# mainboard_ESP32_DevBoard.net
KiCad netlist of a schematic drawn in EAGLE
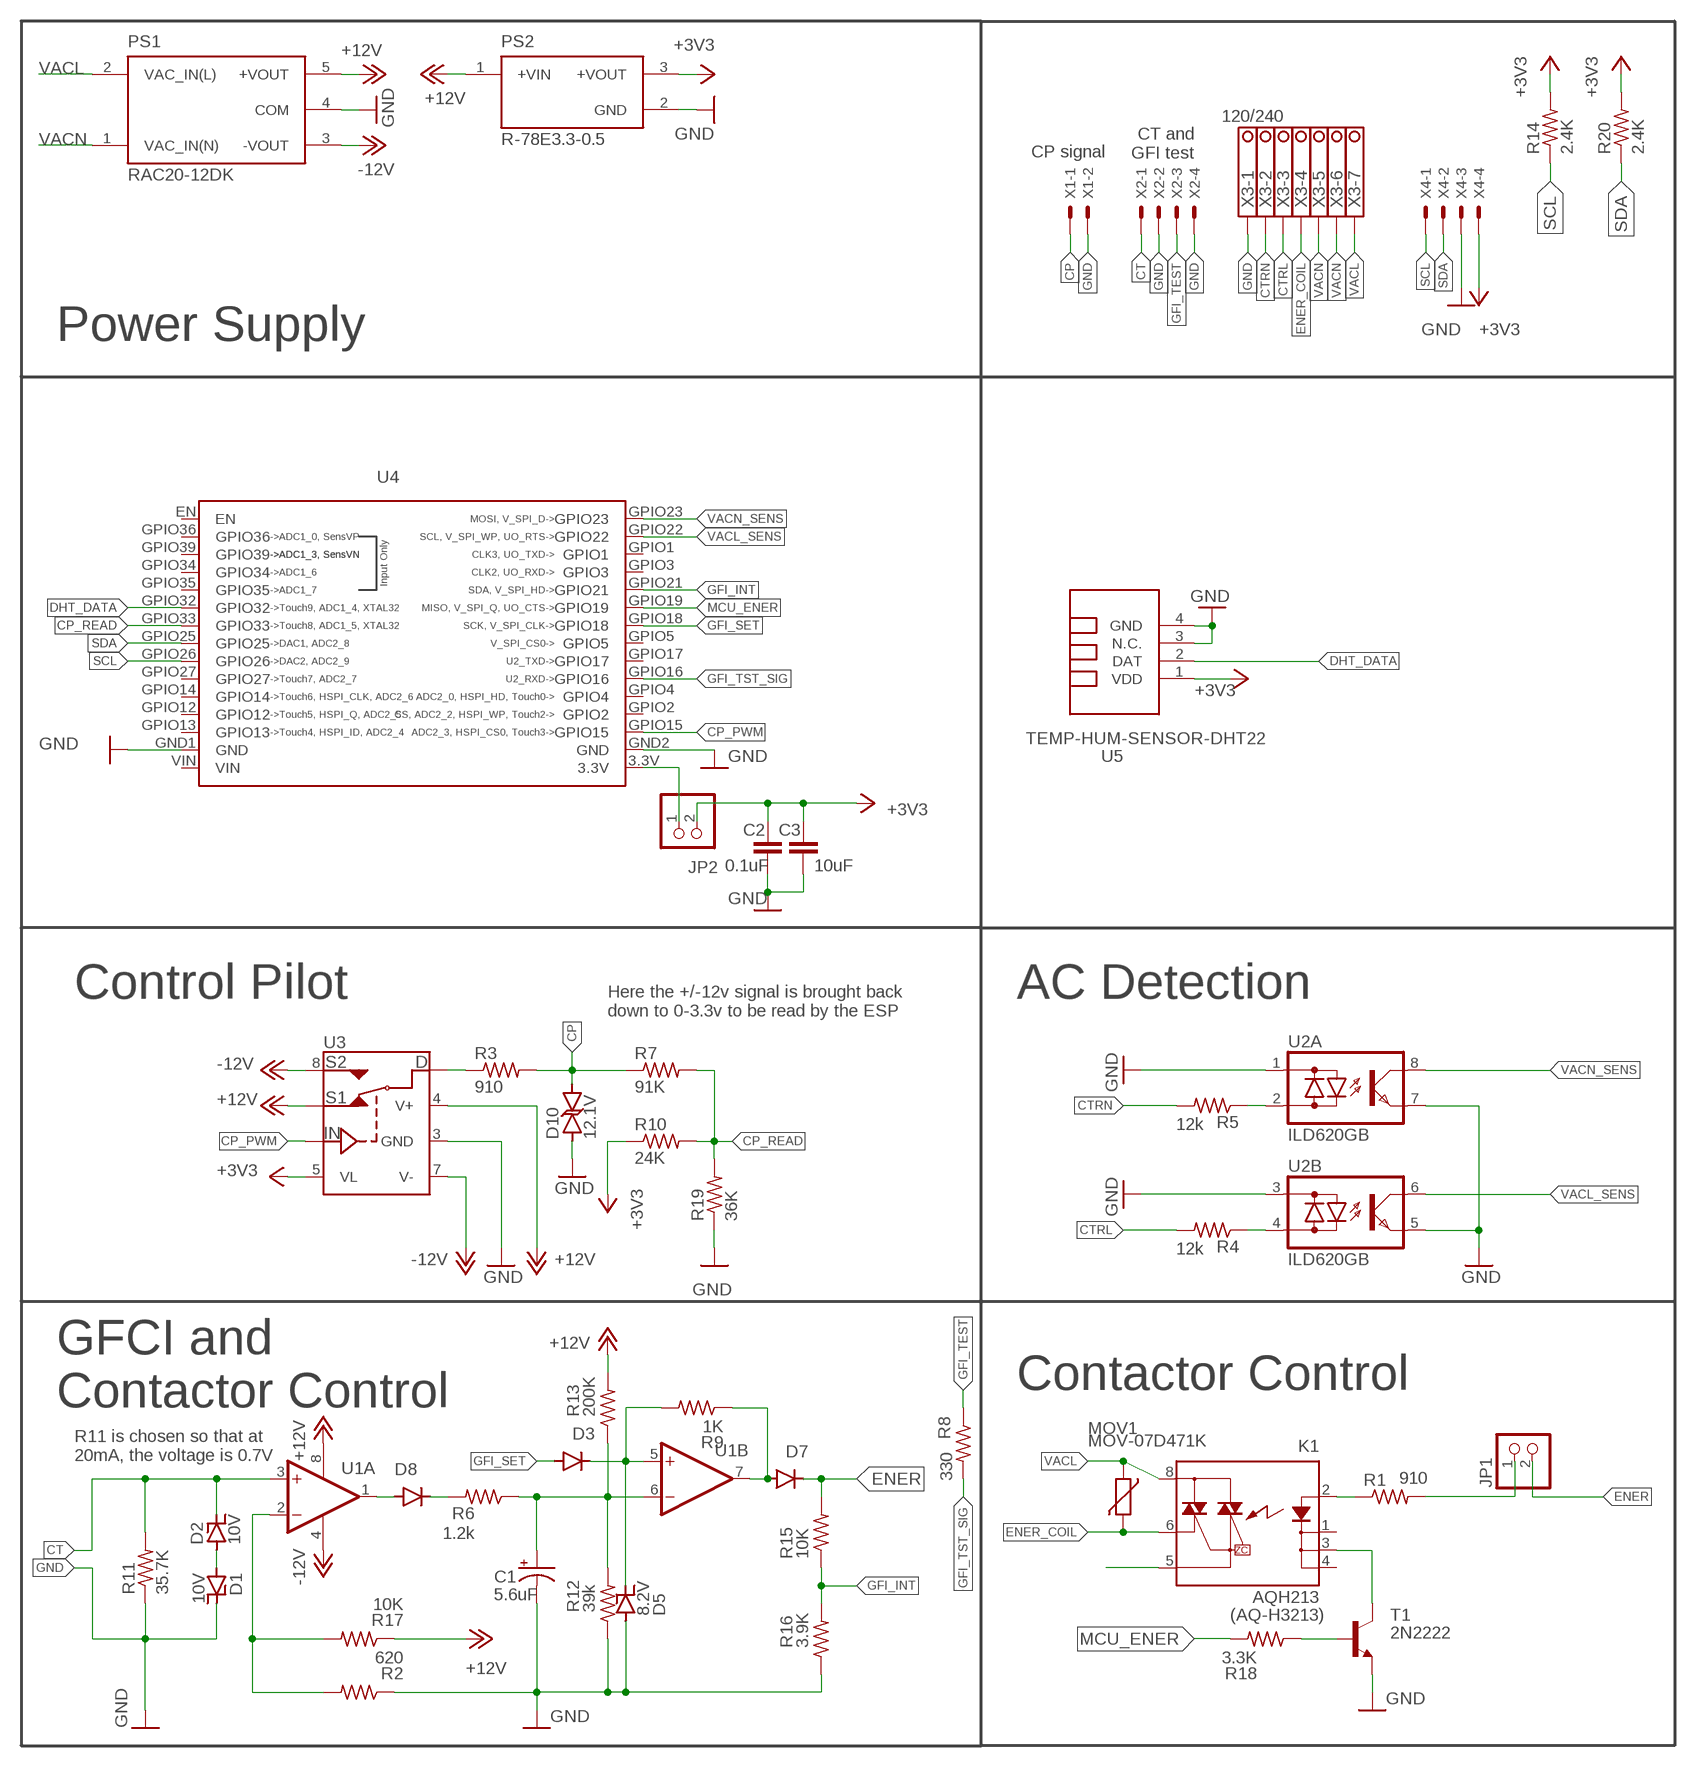
[diagram p0: schematic, sheet 1]

(export (version "E")
  (design (tool "Eeschema 10.0.6"))
  (components
    (comp (ref "C1")
      (value "5.6uF")
      (footprint "eagle-import:E2-5")
      (libsource (lib "eagle-import") (part "CPOL-USE2-5"))
    )
    (comp (ref "C2")
      (value "0.1uF")
      (footprint "eagle-import:C025-025X050")
      (libsource (lib "eagle-import") (part "C-EU025-025X050"))
    )
    (comp (ref "C3")
      (value "10uF")
      (footprint "eagle-import:C025-050X050")
      (libsource (lib "eagle-import") (part "C-EU025-050X050"))
    )
    (comp (ref "D1")
      (value "10V")
      (footprint "eagle-import:DO35-7")
      (libsource (lib "eagle-import") (part "ZENER"))
    )
    (comp (ref "D2")
      (value "10V")
      (footprint "eagle-import:DO35-7")
      (libsource (lib "eagle-import") (part "ZENER"))
    )
    (comp (ref "D3")
      (value "1N4148DO35-7")
      (footprint "eagle-import:DO35-7")
      (libsource (lib "eagle-import") (part "1N4148DO35-7"))
    )
    (comp (ref "D5")
      (value "8.2V")
      (footprint "eagle-import:DO35-7")
      (libsource (lib "eagle-import") (part "ZENER"))
    )
    (comp (ref "D7")
      (value "1N4148DO35-7")
      (footprint "eagle-import:DO35-7")
      (libsource (lib "eagle-import") (part "1N4148DO35-7"))
    )
    (comp (ref "D8")
      (value "1N4148DO35-7")
      (footprint "eagle-import:DO35-7")
      (libsource (lib "eagle-import") (part "1N4148DO35-7"))
    )
    (comp (ref "D10")
      (value "12.1V")
      (footprint "eagle-import:DO15")
      (libsource (lib "eagle-import") (part "P6KE15CAL"))
    )
    (comp (ref "JP1")
      (value "PINHD-1X2")
      (footprint "eagle-import:1X02")
      (libsource (lib "eagle-import") (part "PINHD-1X2"))
    )
    (comp (ref "JP2")
      (value "PINHD-1X2/90")
      (footprint "eagle-import:1X02_90")
      (libsource (lib "eagle-import") (part "PINHD-1X2/90"))
    )
    (comp (ref "K1")
      (value "AQH213")
      (footprint "eagle-import:DIL07")
      (libsource (lib "eagle-import") (part "AQH213"))
    )
    (comp (ref "MOV1")
      (value "MOV-07D471K")
      (footprint "eagle-import:DISC-7")
      (libsource (lib "eagle-import") (part "MOV-07D471K"))
    )
    (comp (ref "PS1")
      (value "RAC20-12DK")
      (footprint "eagle-import:CONV_RAC20-12DK")
      (fields (field (name "DIGI-KEY_PART_NUMBER") "945-3239-ND") (field (name "MF") "Recom Power"))
      (libsource (lib "eagle-import") (part "RAC20-12DK"))
    )
    (comp (ref "PS2")
      (value "R-78E3.3-0.5")
      (footprint "eagle-import:CONV_R-78E3.3-0.5")
      (fields (field (name "DIGI-KEY_PART_NUMBER") "945-1661-5-ND") (field (name "MF") "Recom Power"))
      (libsource (lib "eagle-import") (part "R-78E3.3-0.5"))
    )
    (comp (ref "R1")
      (value "910")
      (footprint "eagle-import:0204_7-L")
      (libsource (lib "eagle-import") (part "RESISTORL"))
    )
    (comp (ref "R2")
      (value "620")
      (footprint "eagle-import:0204_7-L")
      (libsource (lib "eagle-import") (part "RESISTORL"))
    )
    (comp (ref "R3")
      (value "910")
      (footprint "eagle-import:0204_7-L")
      (libsource (lib "eagle-import") (part "RESISTORL"))
    )
    (comp (ref "R4")
      (value "12k")
      (footprint "eagle-import:0204_7-L")
      (libsource (lib "eagle-import") (part "RESISTORL"))
    )
    (comp (ref "R5")
      (value "12k")
      (footprint "eagle-import:0204_7-L")
      (libsource (lib "eagle-import") (part "RESISTORL"))
    )
    (comp (ref "R6")
      (value "1.2k")
      (footprint "eagle-import:0204_7-L")
      (libsource (lib "eagle-import") (part "RESISTORL"))
    )
    (comp (ref "R7")
      (value "91K")
      (footprint "eagle-import:0204_7-L")
      (libsource (lib "eagle-import") (part "RESISTORL"))
    )
    (comp (ref "R8")
      (value "330")
      (footprint "eagle-import:0204_7-L")
      (libsource (lib "eagle-import") (part "RESISTORL"))
    )
    (comp (ref "R9")
      (value "1K")
      (footprint "eagle-import:0204_7-L")
      (libsource (lib "eagle-import") (part "RESISTORL"))
    )
    (comp (ref "R10")
      (value "24K")
      (footprint "eagle-import:0204_7-L")
      (libsource (lib "eagle-import") (part "RESISTORL"))
    )
    (comp (ref "R11")
      (value "35.7K")
      (footprint "eagle-import:0204_7-L")
      (libsource (lib "eagle-import") (part "RESISTORL"))
    )
    (comp (ref "R12")
      (value "39k")
      (footprint "eagle-import:0204_7-L")
      (libsource (lib "eagle-import") (part "RESISTORL"))
    )
    (comp (ref "R13")
      (value "200K")
      (footprint "eagle-import:0204_7-L")
      (libsource (lib "eagle-import") (part "RESISTORL"))
    )
    (comp (ref "R14")
      (value "2.4K")
      (footprint "eagle-import:0204_7-L")
      (libsource (lib "eagle-import") (part "RESISTORL"))
    )
    (comp (ref "R15")
      (value "10K")
      (footprint "eagle-import:0204_7-L")
      (libsource (lib "eagle-import") (part "RESISTORL"))
    )
    (comp (ref "R16")
      (value "3.9K")
      (footprint "eagle-import:0204_7-L")
      (libsource (lib "eagle-import") (part "RESISTORL"))
    )
    (comp (ref "R17")
      (value "10K")
      (footprint "eagle-import:0204_7-L")
      (libsource (lib "eagle-import") (part "RESISTORL"))
    )
    (comp (ref "R18")
      (value "3.3K")
      (footprint "eagle-import:0204_7-L")
      (libsource (lib "eagle-import") (part "RESISTORL"))
    )
    (comp (ref "R19")
      (value "36K")
      (footprint "eagle-import:0204_7-L")
      (libsource (lib "eagle-import") (part "RESISTORL"))
    )
    (comp (ref "R20")
      (value "2.4K")
      (footprint "eagle-import:0204_7-L")
      (libsource (lib "eagle-import") (part "RESISTORL"))
    )
    (comp (ref "T1")
      (value "2N2222")
      (footprint "eagle-import:TO92-EBC")
      (libsource (lib "eagle-import") (part "-NPN-TO92-EBC2N2222"))
    )
    (comp (ref "U1")
      (value "LM833N")
      (footprint "eagle-import:DIL08-LONG")
      (libsource (lib "eagle-import") (part "LM833N"))
    )
    (comp (ref "U2")
      (value "ILD620GB")
      (footprint "eagle-import:DIL8")
      (libsource (lib "eagle-import") (part "ILD620GB"))
    )
    (comp (ref "U3")
      (value "DG419DJ-L")
      (footprint "eagle-import:DIL08-LONG")
      (libsource (lib "eagle-import") (part "DG419DJ-L"))
    )
    (comp (ref "U4")
      (value "ESP32-DOIT-V1")
      (footprint "eagle-import:ESP32-DOIT-V1")
      (libsource (lib "eagle-import") (part "ESP32-DOIT-V1"))
    )
    (comp (ref "U5")
      (value "TEMP-HUM-SENSOR-DHT22")
      (footprint "eagle-import:TEMP-HUM-SENSOR-DHT22")
      (libsource (lib "eagle-import") (part "TEMP-HUM-SENSOR-DHT22"))
    )
    (comp (ref "X1")
      (value "JST-XH-02-PIN-LONG-PAD")
      (footprint "eagle-import:JST-XH-02-PACKAGE-LONG-PAD")
      (libsource (lib "eagle-import") (part "JST-XH-02-PIN-LONG-PAD"))
    )
    (comp (ref "X2")
      (value "JST-XH-04-PIN-LONG-PAD")
      (footprint "eagle-import:JST-XH-04-PACKAGE-LONG-PAD")
      (libsource (lib "eagle-import") (part "JST-XH-04-PIN-LONG-PAD"))
    )
    (comp (ref "X3")
      (value "1751293")
      (footprint "eagle-import:1751293")
      (libsource (lib "eagle-import") (part "1751293"))
    )
    (comp (ref "X4")
      (value "JST-XH-04-PIN-LONG-PAD")
      (footprint "eagle-import:JST-XH-04-PACKAGE-LONG-PAD")
      (libsource (lib "eagle-import") (part "JST-XH-04-PIN-LONG-PAD"))
    )
  )
  (nets
    (net (code "1") (name "+3V3") (class "Default")
      (node (ref "C2") (pin "1") (pinfunction "1_1") (pintype "passive"))
      (node (ref "C3") (pin "1") (pinfunction "1_1") (pintype "passive"))
      (node (ref "JP2") (pin "2") (pinfunction "2_2") (pintype "passive"))
      (node (ref "PS2") (pin "3") (pinfunction "+VOUT_3") (pintype "output"))
      (node (ref "R10") (pin "1") (pinfunction "1_1") (pintype "passive"))
      (node (ref "R14") (pin "2") (pinfunction "2_2") (pintype "passive"))
      (node (ref "R20") (pin "2") (pinfunction "2_2") (pintype "passive"))
      (node (ref "U3") (pin "5") (pinfunction "VL_5") (pintype "bidirectional"))
      (node (ref "U5") (pin "1") (pinfunction "VDD_1") (pintype "power_in"))
      (node (ref "X4") (pin "4") (pinfunction "S_4") (pintype "passive"))
    )
    (net (code "2") (name "+12V") (class "Default")
      (node (ref "PS1") (pin "5") (pinfunction "+VOUT_5") (pintype "output"))
      (node (ref "PS2") (pin "1") (pinfunction "+VIN_1") (pintype "input"))
      (node (ref "R13") (pin "2") (pinfunction "2_2") (pintype "passive"))
      (node (ref "R17") (pin "1") (pinfunction "1_1") (pintype "passive"))
      (node (ref "U1") (pin "8") (pinfunction "V+_8") (pintype "power_in"))
      (node (ref "U3") (pin "2") (pinfunction "S1_2") (pintype "input"))
      (node (ref "U3") (pin "4") (pinfunction "V+_4") (pintype "bidirectional"))
    )
    (net (code "3") (name "-12V") (class "Default")
      (node (ref "PS1") (pin "3") (pinfunction "-VOUT_3") (pintype "output"))
      (node (ref "U1") (pin "4") (pinfunction "V-_4") (pintype "power_in"))
      (node (ref "U3") (pin "7") (pinfunction "V-_7") (pintype "bidirectional"))
      (node (ref "U3") (pin "8") (pinfunction "S2_8") (pintype "input"))
    )
    (net (code "4") (name "/VIN") (class "Default")
      (node (ref "U4") (pin "VIN") (pinfunction "VIN_VIN") (pintype "power_in"))
    )
    (net (code "5") (name "CP") (class "Default")
      (node (ref "D10") (pin "C") (pinfunction "C_C") (pintype "passive"))
      (node (ref "R3") (pin "2") (pinfunction "2_2") (pintype "passive"))
      (node (ref "R7") (pin "1") (pinfunction "1_1") (pintype "passive"))
      (node (ref "X1") (pin "1") (pinfunction "S_1") (pintype "passive"))
    )
    (net (code "6") (name "CP_PWM") (class "Default")
      (node (ref "U3") (pin "6") (pinfunction "IN_6") (pintype "bidirectional"))
      (node (ref "U4") (pin "GPIO15") (pinfunction "GPIO15_GPIO15") (pintype "bidirectional"))
    )
    (net (code "7") (name "CP_READ") (class "Default")
      (node (ref "R10") (pin "2") (pinfunction "2_2") (pintype "passive"))
      (node (ref "R19") (pin "2") (pinfunction "2_2") (pintype "passive"))
      (node (ref "R7") (pin "2") (pinfunction "2_2") (pintype "passive"))
      (node (ref "U4") (pin "GPIO33") (pinfunction "GPIO33_GPIO33") (pintype "bidirectional"))
    )
    (net (code "8") (name "CT") (class "Default")
      (node (ref "D2") (pin "C") (pinfunction "C_C") (pintype "passive"))
      (node (ref "R11") (pin "2") (pinfunction "2_2") (pintype "passive"))
      (node (ref "U1") (pin "3") (pinfunction "+IN_3") (pintype "input"))
      (node (ref "X2") (pin "1") (pinfunction "S_1") (pintype "passive"))
    )
    (net (code "9") (name "CTRL") (class "Default")
      (node (ref "R4") (pin "2") (pinfunction "2_2") (pintype "passive"))
      (node (ref "X3") (pin "3") (pinfunction "K_3") (pintype "passive"))
    )
    (net (code "10") (name "CTRN") (class "Default")
      (node (ref "R5") (pin "2") (pinfunction "2_2") (pintype "passive"))
      (node (ref "X3") (pin "2") (pinfunction "K_2") (pintype "passive"))
    )
    (net (code "11") (name "DHT_DATA") (class "Default")
      (node (ref "U4") (pin "GPIO32") (pinfunction "GPIO32_GPIO32") (pintype "bidirectional"))
      (node (ref "U5") (pin "2") (pinfunction "DAT_2") (pintype "bidirectional"))
    )
    (net (code "12") (name "ENER") (class "Default")
      (node (ref "D7") (pin "C") (pinfunction "C_C") (pintype "passive"))
      (node (ref "JP1") (pin "2") (pinfunction "2_2") (pintype "passive"))
      (node (ref "R15") (pin "2") (pinfunction "2_2") (pintype "passive"))
    )
    (net (code "13") (name "ENER_COIL") (class "Default")
      (node (ref "K1") (pin "6") (pinfunction "DS3_6") (pintype "passive"))
      (node (ref "MOV1") (pin "P$2") (pinfunction "2_P$2") (pintype "passive"))
      (node (ref "X3") (pin "4") (pinfunction "K_4") (pintype "passive"))
    )
    (net (code "14") (name "GFI_INT") (class "Default")
      (node (ref "R15") (pin "1") (pinfunction "1_1") (pintype "passive"))
      (node (ref "R16") (pin "2") (pinfunction "2_2") (pintype "passive"))
      (node (ref "U4") (pin "GPIO21") (pinfunction "GPIO21_GPIO21") (pintype "bidirectional"))
    )
    (net (code "15") (name "GFI_SET") (class "Default")
      (node (ref "D3") (pin "A") (pinfunction "A_A") (pintype "passive"))
      (node (ref "U4") (pin "GPIO18") (pinfunction "GPIO18_GPIO18") (pintype "bidirectional"))
    )
    (net (code "16") (name "GFI_TEST") (class "Default")
      (node (ref "R8") (pin "1") (pinfunction "1_1") (pintype "passive"))
      (node (ref "X2") (pin "3") (pinfunction "S_3") (pintype "passive"))
    )
    (net (code "17") (name "GFI_TST_SIG") (class "Default")
      (node (ref "R8") (pin "2") (pinfunction "2_2") (pintype "passive"))
      (node (ref "U4") (pin "GPIO16") (pinfunction "GPIO16_GPIO16") (pintype "bidirectional"))
    )
    (net (code "18") (name "GND") (class "Default")
      (node (ref "C1") (pin "-") (pinfunction "-_-") (pintype "passive"))
      (node (ref "C2") (pin "2") (pinfunction "2_2") (pintype "passive"))
      (node (ref "C3") (pin "2") (pinfunction "2_2") (pintype "passive"))
      (node (ref "D1") (pin "C") (pinfunction "C_C") (pintype "passive"))
      (node (ref "D10") (pin "A") (pinfunction "A_A") (pintype "passive"))
      (node (ref "D5") (pin "A") (pinfunction "A_A") (pintype "passive"))
      (node (ref "PS1") (pin "4") (pinfunction "COM_4") (pintype "power_in"))
      (node (ref "PS2") (pin "2") (pinfunction "GND_2") (pintype "power_in"))
      (node (ref "R11") (pin "1") (pinfunction "1_1") (pintype "passive"))
      (node (ref "R12") (pin "1") (pinfunction "1_1") (pintype "passive"))
      (node (ref "R16") (pin "1") (pinfunction "1_1") (pintype "passive"))
      (node (ref "R19") (pin "1") (pinfunction "1_1") (pintype "passive"))
      (node (ref "R2") (pin "1") (pinfunction "1_1") (pintype "passive"))
      (node (ref "T1") (pin "E") (pinfunction "E_E") (pintype "passive"))
      (node (ref "U2") (pin "1") (pinfunction "AC1_1") (pintype "passive"))
      (node (ref "U2") (pin "3") (pinfunction "AC1_3") (pintype "passive"))
      (node (ref "U2") (pin "5") (pinfunction "E_5") (pintype "passive"))
      (node (ref "U2") (pin "7") (pinfunction "E_7") (pintype "passive"))
      (node (ref "U3") (pin "3") (pinfunction "GND_3") (pintype "bidirectional"))
      (node (ref "U4") (pin "GND1") (pinfunction "GND_GND1") (pintype "power_in"))
      (node (ref "U4") (pin "GND2") (pinfunction "GND_GND2") (pintype "power_in"))
      (node (ref "U5") (pin "3") (pinfunction "N.C._3") (pintype "passive"))
      (node (ref "U5") (pin "4") (pinfunction "GND_4") (pintype "power_in"))
      (node (ref "X1") (pin "2") (pinfunction "S_2") (pintype "passive"))
      (node (ref "X2") (pin "2") (pinfunction "S_2") (pintype "passive"))
      (node (ref "X2") (pin "4") (pinfunction "S_4") (pintype "passive"))
      (node (ref "X3") (pin "1") (pinfunction "K_1") (pintype "passive"))
      (node (ref "X4") (pin "3") (pinfunction "S_3") (pintype "passive"))
    )
    (net (code "19") (name "MCU_ENER") (class "Default")
      (node (ref "R18") (pin "2") (pinfunction "2_2") (pintype "passive"))
      (node (ref "U4") (pin "GPIO19") (pinfunction "GPIO19_GPIO19") (pintype "bidirectional"))
    )
    (net (code "20") (name "Net-(D1-PadA)") (class "Default")
      (node (ref "D1") (pin "A") (pinfunction "A_A") (pintype "passive"))
      (node (ref "D2") (pin "A") (pinfunction "A_A") (pintype "passive"))
    )
    (net (code "21") (name "Net-(D8-PadC)") (class "Default")
      (node (ref "D8") (pin "C") (pinfunction "C_C") (pintype "passive"))
      (node (ref "R6") (pin "2") (pinfunction "2_2") (pintype "passive"))
    )
    (net (code "22") (name "Net-(JP1-Pad1)") (class "Default")
      (node (ref "JP1") (pin "1") (pinfunction "1_1") (pintype "passive"))
      (node (ref "R1") (pin "2") (pinfunction "2_2") (pintype "passive"))
    )
    (net (code "23") (name "Net-(JP2-Pad1)") (class "Default")
      (node (ref "JP2") (pin "1") (pinfunction "1_1") (pintype "passive"))
      (node (ref "U4") (pin "3.3V") (pinfunction "3.3V_3.3V") (pintype "power_in"))
    )
    (net (code "24") (name "Net-(K1-A)") (class "Default")
      (node (ref "K1") (pin "2") (pinfunction "A_2") (pintype "passive"))
      (node (ref "R1") (pin "1") (pinfunction "1_1") (pintype "passive"))
    )
    (net (code "25") (name "Net-(K1-K1)") (class "Default")
      (node (ref "K1") (pin "3") (pinfunction "K1_3") (pintype "passive"))
      (node (ref "T1") (pin "C") (pinfunction "C_C") (pintype "passive"))
    )
    (net (code "26") (name "Net-(R18-Pad1)") (class "Default")
      (node (ref "R18") (pin "1") (pinfunction "1_1") (pintype "passive"))
      (node (ref "T1") (pin "B") (pinfunction "B_B") (pintype "passive"))
    )
    (net (code "27") (name "Net-(U1A--IN)") (class "Default")
      (node (ref "R17") (pin "2") (pinfunction "2_2") (pintype "passive"))
      (node (ref "R2") (pin "2") (pinfunction "2_2") (pintype "passive"))
      (node (ref "U1") (pin "2") (pinfunction "-IN_2") (pintype "input"))
    )
    (net (code "28") (name "Net-(U1A-OUT)") (class "Default")
      (node (ref "D8") (pin "A") (pinfunction "A_A") (pintype "passive"))
      (node (ref "U1") (pin "1") (pinfunction "OUT_1") (pintype "output"))
    )
    (net (code "29") (name "Net-(U1B-+IN)") (class "Default")
      (node (ref "D3") (pin "C") (pinfunction "C_C") (pintype "passive"))
      (node (ref "D5") (pin "C") (pinfunction "C_C") (pintype "passive"))
      (node (ref "R9") (pin "2") (pinfunction "2_2") (pintype "passive"))
      (node (ref "U1") (pin "5") (pinfunction "+IN_5") (pintype "input"))
    )
    (net (code "30") (name "Net-(U1B--IN)") (class "Default")
      (node (ref "C1") (pin "+") (pinfunction "+_+") (pintype "passive"))
      (node (ref "R12") (pin "2") (pinfunction "2_2") (pintype "passive"))
      (node (ref "R13") (pin "1") (pinfunction "1_1") (pintype "passive"))
      (node (ref "R6") (pin "1") (pinfunction "1_1") (pintype "passive"))
      (node (ref "U1") (pin "6") (pinfunction "-IN_6") (pintype "input"))
    )
    (net (code "31") (name "Net-(U1B-OUT)") (class "Default")
      (node (ref "D7") (pin "A") (pinfunction "A_A") (pintype "passive"))
      (node (ref "R9") (pin "1") (pinfunction "1_1") (pintype "passive"))
      (node (ref "U1") (pin "7") (pinfunction "OUT_7") (pintype "output"))
    )
    (net (code "32") (name "Net-(U2A-AC2)") (class "Default")
      (node (ref "R5") (pin "1") (pinfunction "1_1") (pintype "passive"))
      (node (ref "U2") (pin "2") (pinfunction "AC2_2") (pintype "passive"))
    )
    (net (code "33") (name "Net-(U2B-AC2)") (class "Default")
      (node (ref "R4") (pin "1") (pinfunction "1_1") (pintype "passive"))
      (node (ref "U2") (pin "4") (pinfunction "AC2_4") (pintype "passive"))
    )
    (net (code "34") (name "Net-(U3-D)") (class "Default")
      (node (ref "R3") (pin "1") (pinfunction "1_1") (pintype "passive"))
      (node (ref "U3") (pin "1") (pinfunction "D_1") (pintype "bidirectional"))
    )
    (net (code "35") (name "SCL") (class "Default")
      (node (ref "R14") (pin "1") (pinfunction "1_1") (pintype "passive"))
      (node (ref "U4") (pin "GPIO26") (pinfunction "GPIO26_GPIO26") (pintype "bidirectional"))
      (node (ref "X4") (pin "1") (pinfunction "S_1") (pintype "passive"))
    )
    (net (code "36") (name "SDA") (class "Default")
      (node (ref "R20") (pin "1") (pinfunction "1_1") (pintype "passive"))
      (node (ref "U4") (pin "GPIO25") (pinfunction "GPIO25_GPIO25") (pintype "bidirectional"))
      (node (ref "X4") (pin "2") (pinfunction "S_2") (pintype "passive"))
    )
    (net (code "37") (name "VACL") (class "Default")
      (node (ref "K1") (pin "8") (pinfunction "DS1_8") (pintype "passive"))
      (node (ref "MOV1") (pin "P$1") (pinfunction "1_P$1") (pintype "passive"))
      (node (ref "PS1") (pin "2") (pinfunction "VAC_IN(L)_2") (pintype "input"))
      (node (ref "X3") (pin "7") (pinfunction "K_7") (pintype "passive"))
    )
    (net (code "38") (name "VACL_SENS") (class "Default")
      (node (ref "U2") (pin "6") (pinfunction "C_6") (pintype "passive"))
      (node (ref "U4") (pin "GPIO22") (pinfunction "GPIO22_GPIO22") (pintype "bidirectional"))
    )
    (net (code "39") (name "VACN") (class "Default")
      (node (ref "PS1") (pin "1") (pinfunction "VAC_IN(N)_1") (pintype "input"))
      (node (ref "X3") (pin "5") (pinfunction "K_5") (pintype "passive"))
      (node (ref "X3") (pin "6") (pinfunction "K_6") (pintype "passive"))
    )
    (net (code "40") (name "VACN_SENS") (class "Default")
      (node (ref "U2") (pin "8") (pinfunction "C_8") (pintype "passive"))
      (node (ref "U4") (pin "GPIO23") (pinfunction "GPIO23_GPIO23") (pintype "bidirectional"))
    )
    (net (code "41") (name "unconnected-(K1-DS2-Pad5)") (class "Default")
      (node (ref "K1") (pin "5") (pinfunction "DS2_5") (pintype "passive"))
    )
    (net (code "42") (name "unconnected-(K1-K-Pad1)") (class "Default")
      (node (ref "K1") (pin "1") (pinfunction "K_1") (pintype "passive"))
    )
    (net (code "43") (name "unconnected-(K1-K2-Pad4)") (class "Default")
      (node (ref "K1") (pin "4") (pinfunction "K2_4") (pintype "passive"))
    )
    (net (code "44") (name "unconnected-(U4-PadEN)") (class "Default")
      (node (ref "U4") (pin "EN") (pinfunction "EN_EN") (pintype "input"))
    )
    (net (code "45") (name "unconnected-(U4-PadGPIO1)") (class "Default")
      (node (ref "U4") (pin "GPIO1") (pinfunction "GPIO1_GPIO1") (pintype "bidirectional"))
    )
    (net (code "46") (name "unconnected-(U4-PadGPIO2)") (class "Default")
      (node (ref "U4") (pin "GPIO2") (pinfunction "GPIO2_GPIO2") (pintype "bidirectional"))
    )
    (net (code "47") (name "unconnected-(U4-PadGPIO3)") (class "Default")
      (node (ref "U4") (pin "GPIO3") (pinfunction "GPIO3_GPIO3") (pintype "bidirectional"))
    )
    (net (code "48") (name "unconnected-(U4-PadGPIO4)") (class "Default")
      (node (ref "U4") (pin "GPIO4") (pinfunction "GPIO4_GPIO4") (pintype "bidirectional"))
    )
    (net (code "49") (name "unconnected-(U4-PadGPIO5)") (class "Default")
      (node (ref "U4") (pin "GPIO5") (pinfunction "GPIO5_GPIO5") (pintype "bidirectional"))
    )
    (net (code "50") (name "unconnected-(U4-PadGPIO12)") (class "Default")
      (node (ref "U4") (pin "GPIO12") (pinfunction "GPIO12_GPIO12") (pintype "bidirectional"))
    )
    (net (code "51") (name "unconnected-(U4-PadGPIO13)") (class "Default")
      (node (ref "U4") (pin "GPIO13") (pinfunction "GPIO13_GPIO13") (pintype "bidirectional"))
    )
    (net (code "52") (name "unconnected-(U4-PadGPIO14)") (class "Default")
      (node (ref "U4") (pin "GPIO14") (pinfunction "GPIO14_GPIO14") (pintype "bidirectional"))
    )
    (net (code "53") (name "unconnected-(U4-PadGPIO17)") (class "Default")
      (node (ref "U4") (pin "GPIO17") (pinfunction "GPIO17_GPIO17") (pintype "bidirectional"))
    )
    (net (code "54") (name "unconnected-(U4-PadGPIO27)") (class "Default")
      (node (ref "U4") (pin "GPIO27") (pinfunction "GPIO27_GPIO27") (pintype "bidirectional"))
    )
    (net (code "55") (name "unconnected-(U4-PadGPIO34)") (class "Default")
      (node (ref "U4") (pin "GPIO34") (pinfunction "GPIO34_GPIO34") (pintype "input"))
    )
    (net (code "56") (name "unconnected-(U4-PadGPIO35)") (class "Default")
      (node (ref "U4") (pin "GPIO35") (pinfunction "GPIO35_GPIO35") (pintype "input"))
    )
    (net (code "57") (name "unconnected-(U4-PadGPIO36)") (class "Default")
      (node (ref "U4") (pin "GPIO36") (pinfunction "GPIO36_GPIO36") (pintype "input"))
    )
    (net (code "58") (name "unconnected-(U4-PadGPIO39)") (class "Default")
      (node (ref "U4") (pin "GPIO39") (pinfunction "GPIO39_GPIO39") (pintype "input"))
    )
  )
)
